# mcu_battery.net
KiCad netlist of a schematic drawn in EAGLE
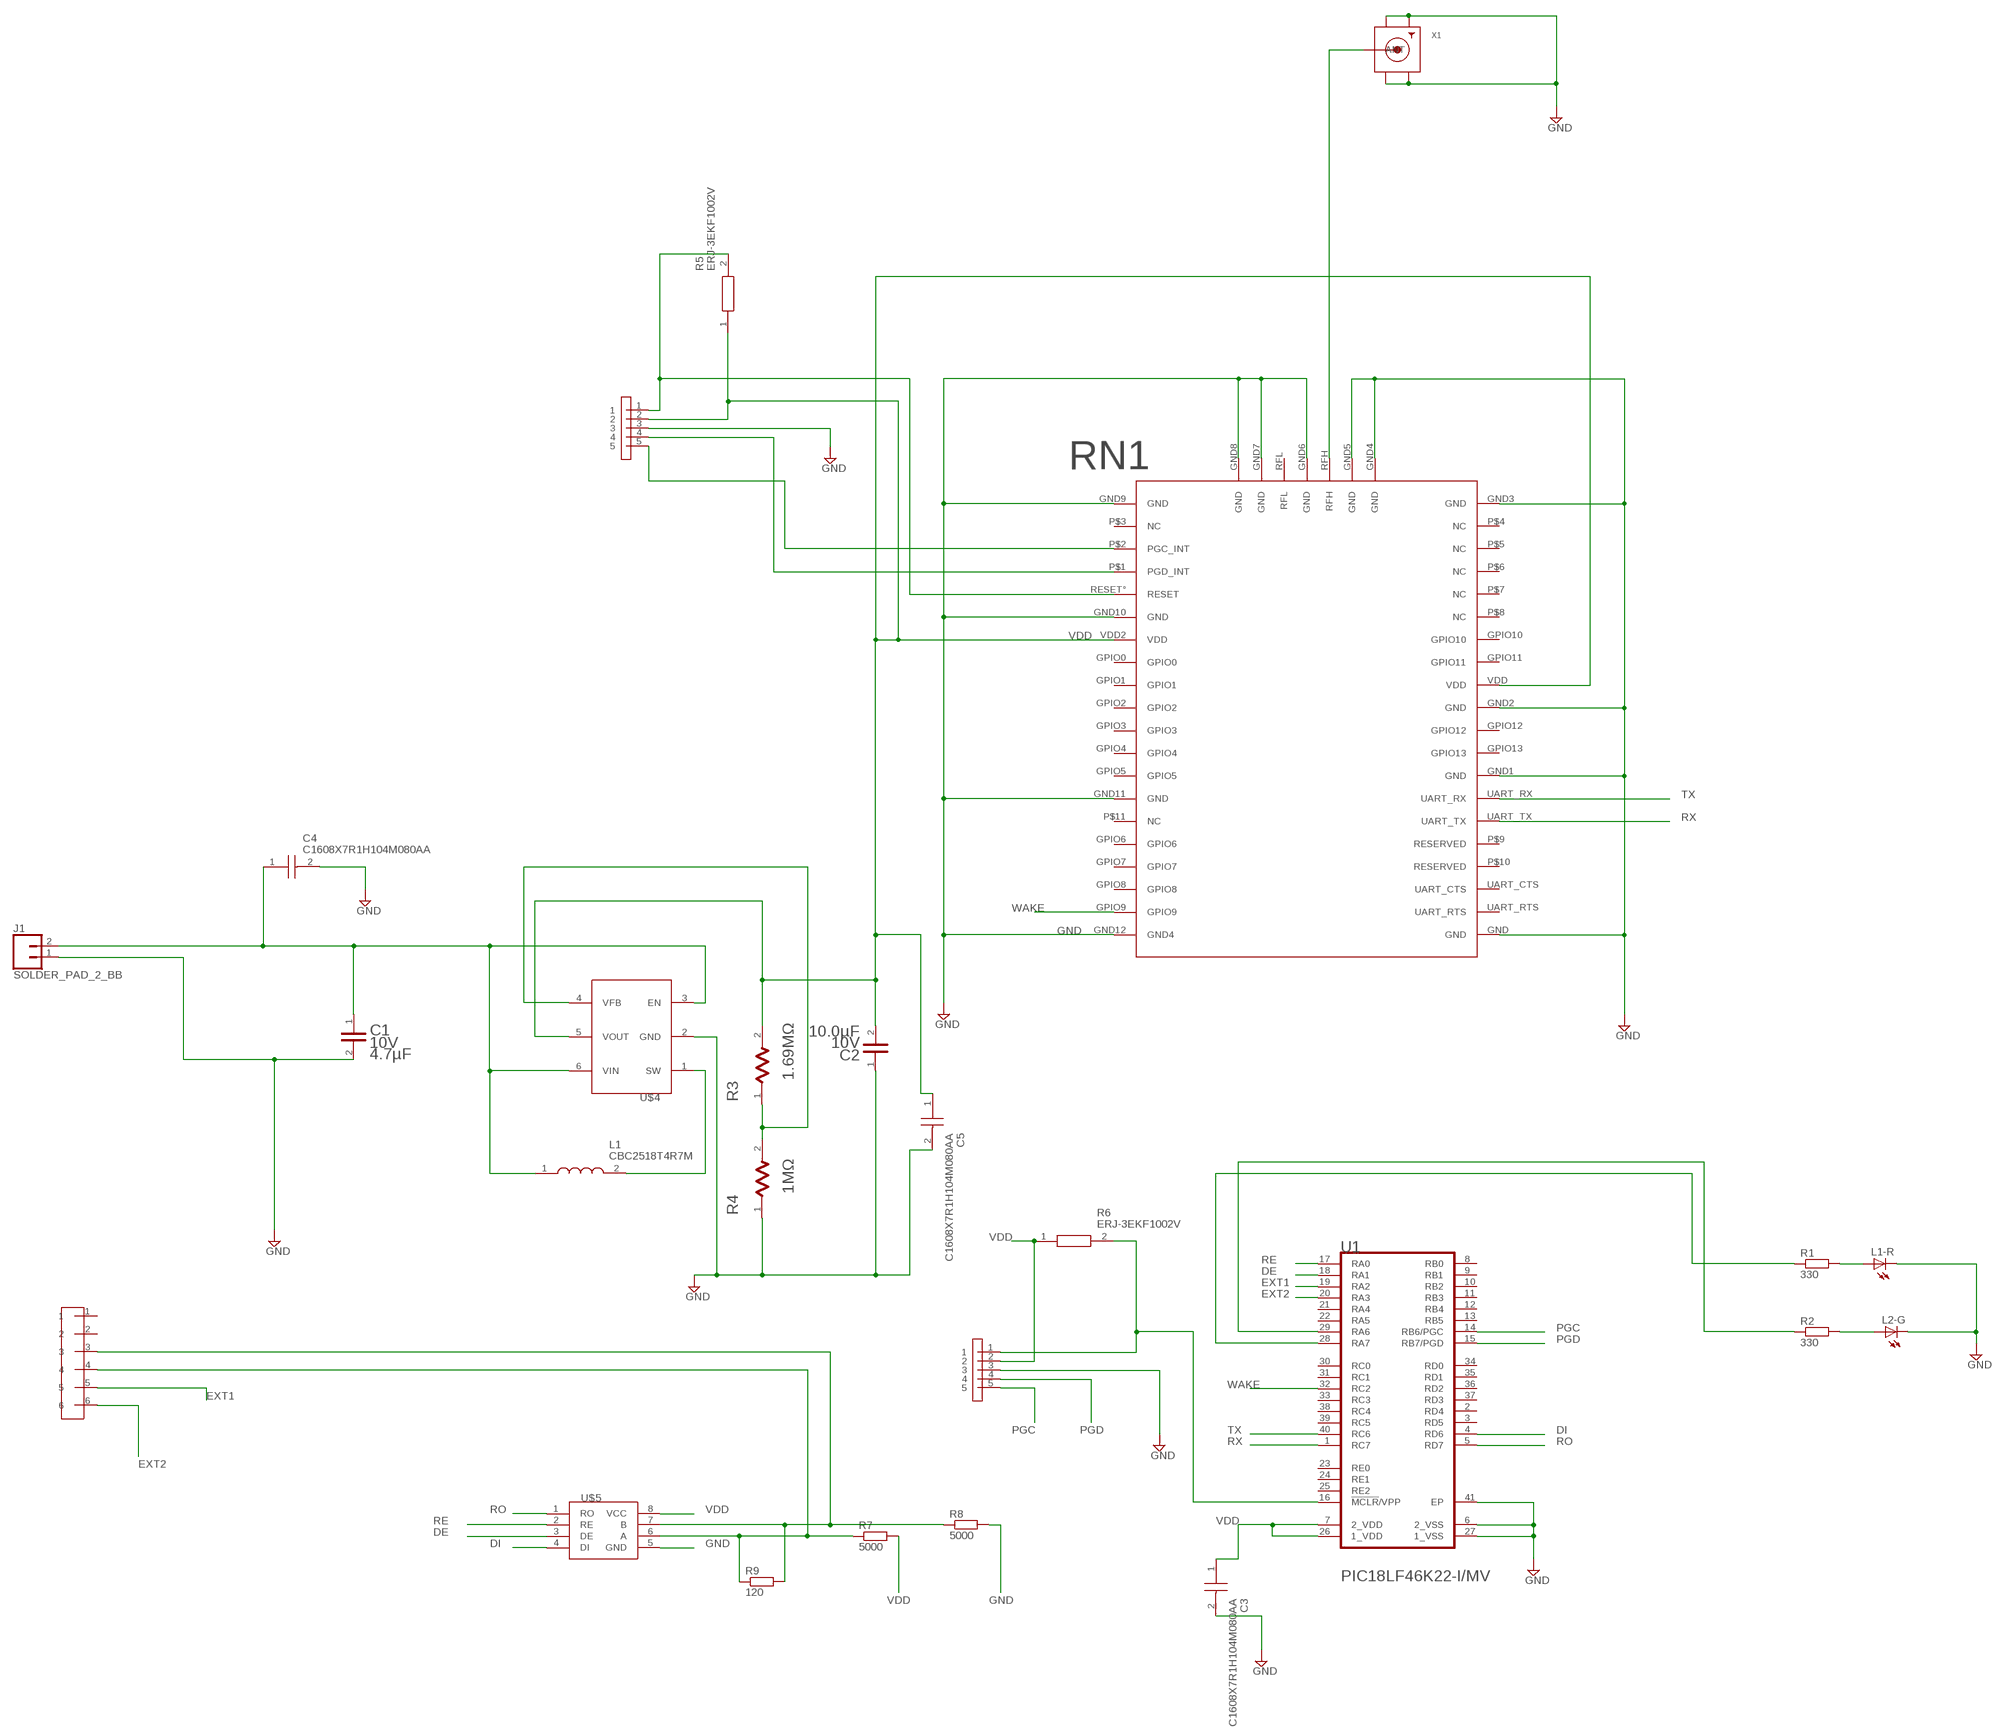
[diagram p0: schematic, sheet 1]

(export (version "E")
  (design (tool "Eeschema 10.0.6"))
  (components
    (comp (ref "C1")
      (value "KEMET_C0603C475K8PACTUKEMET_C0603C475K8PACTU_0_0")
      (footprint "eagle-import:KEMET_C0603C475K8PACTU_0")
      (fields
        (field (name "DIGIKEY_PART_NUMBER") "399-5503-1-ND")
        (field (name "MF") "Kemet")
        (field (name "MOUSER_PART_NUMBER") "80-C0603C475K8P")
      )
      (libsource (lib "eagle-import") (part "KEMET_C0603C475K8PACTUKEMET_C0603C475K8PACTU_0_0"))
    )
    (comp (ref "C2")
      (value "TDK_C1608X5R1A106M080ACTDK_C1608X5R1A106M080AC_0_0")
      (footprint "eagle-import:TDK_C1608X5R1A106M080AC_0")
      (fields
        (field (name "DIGIKEY_PART_NUMBER") "445-6853-1-ND")
        (field (name "MF") "TDK")
        (field (name "MOUSER_PART_NUMBER") "810-C1608X5R1A106M")
      )
      (libsource (lib "eagle-import") (part "TDK_C1608X5R1A106M080ACTDK_C1608X5R1A106M080AC_0_0"))
    )
    (comp (ref "C3")
      (value "C1608X7R1H104M080AA")
      (footprint "eagle-import:CAPC1608X80N")
      (fields (field (name "MOUSER_PART_NUMBER") "810-C1608X7R1H104M"))
      (libsource (lib "eagle-import") (part "C1608X7R1H104M080AA"))
    )
    (comp (ref "C4")
      (value "C1608X7R1H104M080AA")
      (footprint "eagle-import:CAPC1608X80N")
      (fields (field (name "MOUSER_PART_NUMBER") "810-C1608X7R1H104M"))
      (libsource (lib "eagle-import") (part "C1608X7R1H104M080AA"))
    )
    (comp (ref "C5")
      (value "C1608X7R1H104M080AA")
      (footprint "eagle-import:CAPC1608X80N")
      (fields (field (name "MOUSER_PART_NUMBER") "810-C1608X7R1H104M"))
      (libsource (lib "eagle-import") (part "C1608X7R1H104M080AA"))
    )
    (comp (ref "J1")
      (value "SOLDER_PAD_2_BB")
      (footprint "eagle-import:SOLDER_PAD_2")
      (libsource (lib "eagle-import") (part "SOLDER_PAD_2_BB"))
    )
    (comp (ref "L1")
      (value "CBC2518T4R7M")
      (footprint "eagle-import:INDC2518X200N")
      (fields (field (name "MOUSER_PART_NUMBER") "963-CBC2518T4R7M"))
      (libsource (lib "eagle-import") (part "CBC2518T4R7M"))
    )
    (comp (ref "L1-R")
      (value "LEDCHIP-LED0603")
      (footprint "eagle-import:CHIP-LED0603")
      (libsource (lib "eagle-import") (part "LEDCHIP-LED0603"))
    )
    (comp (ref "L2-G")
      (value "LEDCHIP-LED0603")
      (footprint "eagle-import:CHIP-LED0603")
      (libsource (lib "eagle-import") (part "LEDCHIP-LED0603"))
    )
    (comp (ref "R1")
      (value "330")
      (footprint "eagle-import:R0603")
      (libsource (lib "eagle-import") (part "R-EU_R0603"))
    )
    (comp (ref "R2")
      (value "330")
      (footprint "eagle-import:R0603")
      (libsource (lib "eagle-import") (part "R-EU_R0603"))
    )
    (comp (ref "R3")
      (value "VISHAY_CRCW06031M69FKEAVISHAY_CRCW06031M69FKEA_0_1")
      (footprint "eagle-import:VISHAY_CRCW06031M69FKEA_1")
      (fields
        (field (name "APPROVED_ALTERNATE_PART_NUMBER") "541-1.00HHCT-ND")
        (field (name "DIGIKEY_PART_NUMBER") "541-1.69MHTR-ND")
        (field (name "MF") "Vishay")
      )
      (libsource (lib "eagle-import") (part "VISHAY_CRCW06031M69FKEAVISHAY_CRCW06031M69FKEA_0_1"))
    )
    (comp (ref "R4")
      (value "STACKPOLE_RMCF0603FT1M00STACKPOLE_RMCF0603FT1M00_0_1")
      (footprint "eagle-import:STACKPOLE_RMCF0603FT1M00_1")
      (fields
        (field (name "APPROVED_ALTERNATE_PART_NUMBER") "541-1.00HHCT-ND")
        (field (name "DIGIKEY_PART_NUMBER") "RMCF0603FT1M00-ND")
        (field (name "MF") "Stackpole")
      )
      (libsource (lib "eagle-import") (part "STACKPOLE_RMCF0603FT1M00STACKPOLE_RMCF0603FT1M00_0_1"))
    )
    (comp (ref "R5")
      (value "ERJ-3EKF1002V")
      (footprint "eagle-import:RESC1608X55N")
      (fields (field (name "MOUSER_PART_NUMBER") "667-ERJ-3EKF1002V"))
      (libsource (lib "eagle-import") (part "ERJ-3EKF1002V"))
    )
    (comp (ref "R6")
      (value "ERJ-3EKF1002V")
      (footprint "eagle-import:RESC1608X55N")
      (fields (field (name "MOUSER_PART_NUMBER") "667-ERJ-3EKF1002V"))
      (libsource (lib "eagle-import") (part "ERJ-3EKF1002V"))
    )
    (comp (ref "R7")
      (value "5000")
      (footprint "eagle-import:R0805")
      (libsource (lib "eagle-import") (part "R-EU_R0805"))
    )
    (comp (ref "R8")
      (value "5000")
      (footprint "eagle-import:R0805")
      (libsource (lib "eagle-import") (part "R-EU_R0805"))
    )
    (comp (ref "R9")
      (value "120")
      (footprint "eagle-import:R0805")
      (libsource (lib "eagle-import") (part "R-EU_R0805"))
    )
    (comp (ref "RN1")
      (value "NEW_RN2483")
      (footprint "eagle-import:NEW_RN2483")
      (libsource (lib "eagle-import") (part "NEW_RN2483"))
    )
    (comp (ref "U$1")
      (value "CONNECTOR62")
      (footprint "eagle-import:CONNECTOR6")
      (libsource (lib "eagle-import") (part "CONNECTOR62"))
    )
    (comp (ref "U$2")
      (value "ICSP52")
      (footprint "eagle-import:ICSP")
      (libsource (lib "eagle-import") (part "ICSP52"))
    )
    (comp (ref "U$3")
      (value "ICSP52")
      (footprint "eagle-import:ICSP")
      (libsource (lib "eagle-import") (part "ICSP52"))
    )
    (comp (ref "U$4")
      (value "MCP16252")
      (footprint "eagle-import:MCP16252")
      (libsource (lib "eagle-import") (part "MCP16252"))
    )
    (comp (ref "U$5")
      (value "AMD3485E")
      (footprint "eagle-import:AMD3485E")
      (libsource (lib "eagle-import") (part "AMD3485E"))
    )
    (comp (ref "U1")
      (value "MICROCHIP_PIC18LF46K22-I-MVMICROCHIP_PIC18LF46K22-I-MV_0_1")
      (footprint "eagle-import:MICROCHIP_PIC18LF46K22-I-MV_1")
      (fields (field (name "MF") "Microchip") (field (name "MPN") "PIC18LF46K22-I/MV"))
      (libsource (lib "eagle-import") (part "MICROCHIP_PIC18LF46K22-I-MVMICROCHIP_PIC18LF46K22-I-MV_0_1"))
    )
    (comp (ref "X1")
      (value "SMACONNECTOR_EDGE")
      (footprint "eagle-import:SMA_EDGELAUNCH")
      (libsource (lib "eagle-import") (part "SMACONNECTOR_EDGE"))
    )
  )
  (nets
    (net (code "1") (name "/DE") (class "Default")
      (node (ref "U$5") (pin "3") (pinfunction "DE_3") (pintype "bidirectional"))
      (node (ref "U1") (pin "18") (pinfunction "RA1_18") (pintype "bidirectional"))
    )
    (net (code "2") (name "/DI") (class "Default")
      (node (ref "U$5") (pin "4") (pinfunction "DI_4") (pintype "bidirectional"))
      (node (ref "U1") (pin "4") (pinfunction "RD6_4") (pintype "bidirectional"))
    )
    (net (code "3") (name "/EXT1") (class "Default")
      (node (ref "U$1") (pin "5") (pinfunction "5_5") (pintype "bidirectional"))
      (node (ref "U1") (pin "19") (pinfunction "RA2_19") (pintype "bidirectional"))
    )
    (net (code "4") (name "/EXT2") (class "Default")
      (node (ref "U$1") (pin "6") (pinfunction "6_6") (pintype "bidirectional"))
      (node (ref "U1") (pin "20") (pinfunction "RA3_20") (pintype "bidirectional"))
    )
    (net (code "5") (name "/PGC") (class "Default")
      (node (ref "U$2") (pin "5") (pinfunction "5_5") (pintype "bidirectional"))
      (node (ref "U1") (pin "14") (pinfunction "RB6/PGC_14") (pintype "bidirectional"))
    )
    (net (code "6") (name "/PGD") (class "Default")
      (node (ref "U$2") (pin "4") (pinfunction "4_4") (pintype "bidirectional"))
      (node (ref "U1") (pin "15") (pinfunction "RB7/PGD_15") (pintype "bidirectional"))
    )
    (net (code "7") (name "/RE") (class "Default")
      (node (ref "U$5") (pin "2") (pinfunction "RE_2") (pintype "bidirectional"))
      (node (ref "U1") (pin "17") (pinfunction "RA0_17") (pintype "bidirectional"))
    )
    (net (code "8") (name "/RO") (class "Default")
      (node (ref "U$5") (pin "1") (pinfunction "RO_1") (pintype "bidirectional"))
      (node (ref "U1") (pin "5") (pinfunction "RD7_5") (pintype "bidirectional"))
    )
    (net (code "9") (name "/RX") (class "Default")
      (node (ref "RN1") (pin "UART_TX") (pinfunction "UART_TX_UART_TX") (pintype "bidirectional"))
      (node (ref "U1") (pin "1") (pinfunction "RC7_1") (pintype "bidirectional"))
    )
    (net (code "10") (name "/TX") (class "Default")
      (node (ref "RN1") (pin "UART_RX") (pinfunction "UART_RX_UART_RX") (pintype "bidirectional"))
      (node (ref "U1") (pin "40") (pinfunction "RC6_40") (pintype "bidirectional"))
    )
    (net (code "11") (name "/VDD") (class "Default")
      (node (ref "C2") (pin "2") (pinfunction "2_2") (pintype "bidirectional"))
      (node (ref "C3") (pin "1") (pinfunction "1_1") (pintype "bidirectional"))
      (node (ref "C5") (pin "1") (pinfunction "1_1") (pintype "bidirectional"))
      (node (ref "R3") (pin "2") (pinfunction "2_2") (pintype "passive"))
      (node (ref "R5") (pin "1") (pinfunction "1_1") (pintype "bidirectional"))
      (node (ref "R6") (pin "1") (pinfunction "1_1") (pintype "bidirectional"))
      (node (ref "R7") (pin "2") (pinfunction "2_2") (pintype "passive"))
      (node (ref "RN1") (pin "VDD") (pinfunction "VDD_VDD") (pintype "bidirectional"))
      (node (ref "RN1") (pin "VDD2") (pinfunction "VDD_VDD2") (pintype "bidirectional"))
      (node (ref "U$2") (pin "2") (pinfunction "2_2") (pintype "bidirectional"))
      (node (ref "U$3") (pin "2") (pinfunction "2_2") (pintype "bidirectional"))
      (node (ref "U$4") (pin "5") (pinfunction "VOUT_5") (pintype "bidirectional"))
      (node (ref "U$5") (pin "8") (pinfunction "VCC_8") (pintype "bidirectional"))
      (node (ref "U1") (pin "26") (pinfunction "1_VDD_26") (pintype "power_in"))
      (node (ref "U1") (pin "7") (pinfunction "2_VDD_7") (pintype "power_in"))
    )
    (net (code "12") (name "/WAKE") (class "Default")
      (node (ref "RN1") (pin "GPIO9") (pinfunction "GPIO9_GPIO9") (pintype "bidirectional"))
      (node (ref "U1") (pin "32") (pinfunction "RC2_32") (pintype "bidirectional"))
    )
    (net (code "13") (name "GND") (class "Default")
      (node (ref "C1") (pin "2") (pinfunction "2_2") (pintype "bidirectional"))
      (node (ref "C2") (pin "1") (pinfunction "1_1") (pintype "bidirectional"))
      (node (ref "C3") (pin "2") (pinfunction "2_2") (pintype "bidirectional"))
      (node (ref "C4") (pin "2") (pinfunction "2_2") (pintype "bidirectional"))
      (node (ref "C5") (pin "2") (pinfunction "2_2") (pintype "bidirectional"))
      (node (ref "J1") (pin "1") (pinfunction "1_1") (pintype "passive"))
      (node (ref "L1-R") (pin "C") (pinfunction "C_C") (pintype "passive"))
      (node (ref "L2-G") (pin "C") (pinfunction "C_C") (pintype "passive"))
      (node (ref "R4") (pin "1") (pinfunction "1_1") (pintype "passive"))
      (node (ref "R8") (pin "2") (pinfunction "2_2") (pintype "passive"))
      (node (ref "RN1") (pin "GND") (pinfunction "GND_GND") (pintype "bidirectional"))
      (node (ref "RN1") (pin "GND1") (pinfunction "GND_GND1") (pintype "bidirectional"))
      (node (ref "RN1") (pin "GND10") (pinfunction "GND_GND10") (pintype "bidirectional"))
      (node (ref "RN1") (pin "GND11") (pinfunction "GND_GND11") (pintype "bidirectional"))
      (node (ref "RN1") (pin "GND12") (pinfunction "GND4_GND12") (pintype "bidirectional"))
      (node (ref "RN1") (pin "GND2") (pinfunction "GND_GND2") (pintype "bidirectional"))
      (node (ref "RN1") (pin "GND3") (pinfunction "GND_GND3") (pintype "bidirectional"))
      (node (ref "RN1") (pin "GND4") (pinfunction "GND_GND4") (pintype "bidirectional"))
      (node (ref "RN1") (pin "GND5") (pinfunction "GND_GND5") (pintype "bidirectional"))
      (node (ref "RN1") (pin "GND6") (pinfunction "GND_GND6") (pintype "bidirectional"))
      (node (ref "RN1") (pin "GND7") (pinfunction "GND_GND7") (pintype "bidirectional"))
      (node (ref "RN1") (pin "GND8") (pinfunction "GND_GND8") (pintype "bidirectional"))
      (node (ref "RN1") (pin "GND9") (pinfunction "GND_GND9") (pintype "bidirectional"))
      (node (ref "U$2") (pin "3") (pinfunction "3_3") (pintype "bidirectional"))
      (node (ref "U$3") (pin "3") (pinfunction "3_3") (pintype "bidirectional"))
      (node (ref "U$4") (pin "2") (pinfunction "GND_2") (pintype "bidirectional"))
      (node (ref "U$5") (pin "5") (pinfunction "GND_5") (pintype "bidirectional"))
      (node (ref "U1") (pin "27") (pinfunction "1_VSS_27") (pintype "power_in"))
      (node (ref "U1") (pin "41") (pinfunction "EP_41") (pintype "passive"))
      (node (ref "U1") (pin "6") (pinfunction "2_VSS_6") (pintype "power_in"))
      (node (ref "X1") (pin "GND@1") (pinfunction "GND4_GND@1") (pintype "power_in"))
      (node (ref "X1") (pin "GND@2") (pinfunction "GND3_GND@2") (pintype "power_in"))
      (node (ref "X1") (pin "GND@3") (pinfunction "GND2_GND@3") (pintype "power_in"))
      (node (ref "X1") (pin "GND@4") (pinfunction "GND1_GND@4") (pintype "power_in"))
    )
    (net (code "14") (name "Net-(L1-R-PadA)") (class "Default")
      (node (ref "L1-R") (pin "A") (pinfunction "A_A") (pintype "passive"))
      (node (ref "R1") (pin "2") (pinfunction "2_2") (pintype "passive"))
    )
    (net (code "15") (name "Net-(L2-G-PadA)") (class "Default")
      (node (ref "L2-G") (pin "A") (pinfunction "A_A") (pintype "passive"))
      (node (ref "R2") (pin "2") (pinfunction "2_2") (pintype "passive"))
    )
    (net (code "16") (name "Net-(RN1-PGC_INT)") (class "Default")
      (node (ref "RN1") (pin "P$2") (pinfunction "PGC_INT_P$2") (pintype "bidirectional"))
      (node (ref "U$3") (pin "5") (pinfunction "5_5") (pintype "bidirectional"))
    )
    (net (code "17") (name "Net-(RN1-PGD_INT)") (class "Default")
      (node (ref "RN1") (pin "P$1") (pinfunction "PGD_INT_P$1") (pintype "bidirectional"))
      (node (ref "U$3") (pin "4") (pinfunction "4_4") (pintype "bidirectional"))
    )
    (net (code "18") (name "Net-(RN1-RESET)") (class "Default")
      (node (ref "R5") (pin "2") (pinfunction "2_2") (pintype "bidirectional"))
      (node (ref "RN1") (pin "RESET°") (pinfunction "RESET_RESET°") (pintype "bidirectional"))
      (node (ref "U$3") (pin "1") (pinfunction "1_1") (pintype "bidirectional"))
    )
    (net (code "19") (name "Net-(U$4-EN)") (class "Default")
      (node (ref "C1") (pin "1") (pinfunction "1_1") (pintype "bidirectional"))
      (node (ref "C4") (pin "1") (pinfunction "1_1") (pintype "bidirectional"))
      (node (ref "J1") (pin "2") (pinfunction "2_2") (pintype "passive"))
      (node (ref "L1") (pin "1") (pinfunction "1_1") (pintype "bidirectional"))
      (node (ref "U$4") (pin "3") (pinfunction "EN_3") (pintype "bidirectional"))
      (node (ref "U$4") (pin "6") (pinfunction "VIN_6") (pintype "bidirectional"))
    )
    (net (code "20") (name "Net-(U$4-SW)") (class "Default")
      (node (ref "L1") (pin "2") (pinfunction "2_2") (pintype "bidirectional"))
      (node (ref "U$4") (pin "1") (pinfunction "SW_1") (pintype "bidirectional"))
    )
    (net (code "21") (name "Net-(U$4-VFB)") (class "Default")
      (node (ref "R3") (pin "1") (pinfunction "1_1") (pintype "passive"))
      (node (ref "R4") (pin "2") (pinfunction "2_2") (pintype "passive"))
      (node (ref "U$4") (pin "4") (pinfunction "VFB_4") (pintype "bidirectional"))
    )
    (net (code "22") (name "Net-(U$5-A)") (class "Default")
      (node (ref "R7") (pin "1") (pinfunction "1_1") (pintype "passive"))
      (node (ref "R9") (pin "1") (pinfunction "1_1") (pintype "passive"))
      (node (ref "U$1") (pin "4") (pinfunction "4_4") (pintype "bidirectional"))
      (node (ref "U$5") (pin "6") (pinfunction "A_6") (pintype "bidirectional"))
    )
    (net (code "23") (name "Net-(U$5-B)") (class "Default")
      (node (ref "R8") (pin "1") (pinfunction "1_1") (pintype "passive"))
      (node (ref "R9") (pin "2") (pinfunction "2_2") (pintype "passive"))
      (node (ref "U$1") (pin "3") (pinfunction "3_3") (pintype "bidirectional"))
      (node (ref "U$5") (pin "7") (pinfunction "B_7") (pintype "bidirectional"))
    )
    (net (code "24") (name "Net-(U1-RA6)") (class "Default")
      (node (ref "R2") (pin "1") (pinfunction "1_1") (pintype "passive"))
      (node (ref "U1") (pin "29") (pinfunction "RA6_29") (pintype "bidirectional"))
    )
    (net (code "25") (name "Net-(U1-RA7)") (class "Default")
      (node (ref "R1") (pin "1") (pinfunction "1_1") (pintype "passive"))
      (node (ref "U1") (pin "28") (pinfunction "RA7_28") (pintype "bidirectional"))
    )
    (net (code "26") (name "Net-(U1-~{MCLR}{slash}VPP)") (class "Default")
      (node (ref "R6") (pin "2") (pinfunction "2_2") (pintype "bidirectional"))
      (node (ref "U$2") (pin "1") (pinfunction "1_1") (pintype "bidirectional"))
      (node (ref "U1") (pin "16") (pinfunction "~{MCLR}/VPP_16") (pintype "input"))
    )
    (net (code "27") (name "Net-(X1-ANT)") (class "Default")
      (node (ref "RN1") (pin "RFH") (pinfunction "RFH_RFH") (pintype "bidirectional"))
      (node (ref "X1") (pin "P") (pinfunction "ANT_P") (pintype "bidirectional"))
    )
    (net (code "28") (name "unconnected-(RN1-NC-PadP$3)") (class "Default")
      (node (ref "RN1") (pin "P$3") (pinfunction "NC_P$3") (pintype "bidirectional"))
    )
    (net (code "29") (name "unconnected-(RN1-NC-PadP$4)") (class "Default")
      (node (ref "RN1") (pin "P$4") (pinfunction "NC_P$4") (pintype "bidirectional"))
    )
    (net (code "30") (name "unconnected-(RN1-NC-PadP$5)") (class "Default")
      (node (ref "RN1") (pin "P$5") (pinfunction "NC_P$5") (pintype "bidirectional"))
    )
    (net (code "31") (name "unconnected-(RN1-NC-PadP$6)") (class "Default")
      (node (ref "RN1") (pin "P$6") (pinfunction "NC_P$6") (pintype "bidirectional"))
    )
    (net (code "32") (name "unconnected-(RN1-NC-PadP$7)") (class "Default")
      (node (ref "RN1") (pin "P$7") (pinfunction "NC_P$7") (pintype "bidirectional"))
    )
    (net (code "33") (name "unconnected-(RN1-NC-PadP$8)") (class "Default")
      (node (ref "RN1") (pin "P$8") (pinfunction "NC_P$8") (pintype "bidirectional"))
    )
    (net (code "34") (name "unconnected-(RN1-NC-PadP$11)") (class "Default")
      (node (ref "RN1") (pin "P$11") (pinfunction "NC_P$11") (pintype "bidirectional"))
    )
    (net (code "35") (name "unconnected-(RN1-PadGPIO0)") (class "Default")
      (node (ref "RN1") (pin "GPIO0") (pinfunction "GPIO0_GPIO0") (pintype "bidirectional"))
    )
    (net (code "36") (name "unconnected-(RN1-PadGPIO1)") (class "Default")
      (node (ref "RN1") (pin "GPIO1") (pinfunction "GPIO1_GPIO1") (pintype "bidirectional"))
    )
    (net (code "37") (name "unconnected-(RN1-PadGPIO2)") (class "Default")
      (node (ref "RN1") (pin "GPIO2") (pinfunction "GPIO2_GPIO2") (pintype "bidirectional"))
    )
    (net (code "38") (name "unconnected-(RN1-PadGPIO3)") (class "Default")
      (node (ref "RN1") (pin "GPIO3") (pinfunction "GPIO3_GPIO3") (pintype "bidirectional"))
    )
    (net (code "39") (name "unconnected-(RN1-PadGPIO4)") (class "Default")
      (node (ref "RN1") (pin "GPIO4") (pinfunction "GPIO4_GPIO4") (pintype "bidirectional"))
    )
    (net (code "40") (name "unconnected-(RN1-PadGPIO5)") (class "Default")
      (node (ref "RN1") (pin "GPIO5") (pinfunction "GPIO5_GPIO5") (pintype "bidirectional"))
    )
    (net (code "41") (name "unconnected-(RN1-PadGPIO6)") (class "Default")
      (node (ref "RN1") (pin "GPIO6") (pinfunction "GPIO6_GPIO6") (pintype "bidirectional"))
    )
    (net (code "42") (name "unconnected-(RN1-PadGPIO7)") (class "Default")
      (node (ref "RN1") (pin "GPIO7") (pinfunction "GPIO7_GPIO7") (pintype "bidirectional"))
    )
    (net (code "43") (name "unconnected-(RN1-PadGPIO8)") (class "Default")
      (node (ref "RN1") (pin "GPIO8") (pinfunction "GPIO8_GPIO8") (pintype "bidirectional"))
    )
    (net (code "44") (name "unconnected-(RN1-PadGPIO10)") (class "Default")
      (node (ref "RN1") (pin "GPIO10") (pinfunction "GPIO10_GPIO10") (pintype "bidirectional"))
    )
    (net (code "45") (name "unconnected-(RN1-PadGPIO11)") (class "Default")
      (node (ref "RN1") (pin "GPIO11") (pinfunction "GPIO11_GPIO11") (pintype "bidirectional"))
    )
    (net (code "46") (name "unconnected-(RN1-PadGPIO12)") (class "Default")
      (node (ref "RN1") (pin "GPIO12") (pinfunction "GPIO12_GPIO12") (pintype "bidirectional"))
    )
    (net (code "47") (name "unconnected-(RN1-PadGPIO13)") (class "Default")
      (node (ref "RN1") (pin "GPIO13") (pinfunction "GPIO13_GPIO13") (pintype "bidirectional"))
    )
    (net (code "48") (name "unconnected-(RN1-PadRFL)") (class "Default")
      (node (ref "RN1") (pin "RFL") (pinfunction "RFL_RFL") (pintype "bidirectional"))
    )
    (net (code "49") (name "unconnected-(RN1-PadUART_CTS)") (class "Default")
      (node (ref "RN1") (pin "UART_CTS") (pinfunction "UART_CTS_UART_CTS") (pintype "bidirectional"))
    )
    (net (code "50") (name "unconnected-(RN1-PadUART_RTS)") (class "Default")
      (node (ref "RN1") (pin "UART_RTS") (pinfunction "UART_RTS_UART_RTS") (pintype "bidirectional"))
    )
    (net (code "51") (name "unconnected-(RN1-RESERVED-PadP$9)") (class "Default")
      (node (ref "RN1") (pin "P$9") (pinfunction "RESERVED_P$9") (pintype "bidirectional"))
    )
    (net (code "52") (name "unconnected-(RN1-RESERVED-PadP$10)") (class "Default")
      (node (ref "RN1") (pin "P$10") (pinfunction "RESERVED_P$10") (pintype "bidirectional"))
    )
    (net (code "53") (name "unconnected-(U$1-Pad1)") (class "Default")
      (node (ref "U$1") (pin "1") (pinfunction "1_1") (pintype "bidirectional"))
    )
    (net (code "54") (name "unconnected-(U$1-Pad2)") (class "Default")
      (node (ref "U$1") (pin "2") (pinfunction "2_2") (pintype "bidirectional"))
    )
    (net (code "55") (name "unconnected-(U1-RA4-Pad21)") (class "Default")
      (node (ref "U1") (pin "21") (pinfunction "RA4_21") (pintype "bidirectional"))
    )
    (net (code "56") (name "unconnected-(U1-RA5-Pad22)") (class "Default")
      (node (ref "U1") (pin "22") (pinfunction "RA5_22") (pintype "bidirectional"))
    )
    (net (code "57") (name "unconnected-(U1-RB0-Pad8)") (class "Default")
      (node (ref "U1") (pin "8") (pinfunction "RB0_8") (pintype "bidirectional"))
    )
    (net (code "58") (name "unconnected-(U1-RB1-Pad9)") (class "Default")
      (node (ref "U1") (pin "9") (pinfunction "RB1_9") (pintype "bidirectional"))
    )
    (net (code "59") (name "unconnected-(U1-RB2-Pad10)") (class "Default")
      (node (ref "U1") (pin "10") (pinfunction "RB2_10") (pintype "bidirectional"))
    )
    (net (code "60") (name "unconnected-(U1-RB3-Pad11)") (class "Default")
      (node (ref "U1") (pin "11") (pinfunction "RB3_11") (pintype "bidirectional"))
    )
    (net (code "61") (name "unconnected-(U1-RB4-Pad12)") (class "Default")
      (node (ref "U1") (pin "12") (pinfunction "RB4_12") (pintype "bidirectional"))
    )
    (net (code "62") (name "unconnected-(U1-RB5-Pad13)") (class "Default")
      (node (ref "U1") (pin "13") (pinfunction "RB5_13") (pintype "bidirectional"))
    )
    (net (code "63") (name "unconnected-(U1-RC0-Pad30)") (class "Default")
      (node (ref "U1") (pin "30") (pinfunction "RC0_30") (pintype "bidirectional"))
    )
    (net (code "64") (name "unconnected-(U1-RC1-Pad31)") (class "Default")
      (node (ref "U1") (pin "31") (pinfunction "RC1_31") (pintype "bidirectional"))
    )
    (net (code "65") (name "unconnected-(U1-RC3-Pad33)") (class "Default")
      (node (ref "U1") (pin "33") (pinfunction "RC3_33") (pintype "bidirectional"))
    )
    (net (code "66") (name "unconnected-(U1-RC4-Pad38)") (class "Default")
      (node (ref "U1") (pin "38") (pinfunction "RC4_38") (pintype "bidirectional"))
    )
    (net (code "67") (name "unconnected-(U1-RC5-Pad39)") (class "Default")
      (node (ref "U1") (pin "39") (pinfunction "RC5_39") (pintype "bidirectional"))
    )
    (net (code "68") (name "unconnected-(U1-RD0-Pad34)") (class "Default")
      (node (ref "U1") (pin "34") (pinfunction "RD0_34") (pintype "bidirectional"))
    )
    (net (code "69") (name "unconnected-(U1-RD1-Pad35)") (class "Default")
      (node (ref "U1") (pin "35") (pinfunction "RD1_35") (pintype "bidirectional"))
    )
    (net (code "70") (name "unconnected-(U1-RD2-Pad36)") (class "Default")
      (node (ref "U1") (pin "36") (pinfunction "RD2_36") (pintype "bidirectional"))
    )
    (net (code "71") (name "unconnected-(U1-RD3-Pad37)") (class "Default")
      (node (ref "U1") (pin "37") (pinfunction "RD3_37") (pintype "bidirectional"))
    )
    (net (code "72") (name "unconnected-(U1-RD4-Pad2)") (class "Default")
      (node (ref "U1") (pin "2") (pinfunction "RD4_2") (pintype "bidirectional"))
    )
    (net (code "73") (name "unconnected-(U1-RD5-Pad3)") (class "Default")
      (node (ref "U1") (pin "3") (pinfunction "RD5_3") (pintype "bidirectional"))
    )
    (net (code "74") (name "unconnected-(U1-RE0-Pad23)") (class "Default")
      (node (ref "U1") (pin "23") (pinfunction "RE0_23") (pintype "bidirectional"))
    )
    (net (code "75") (name "unconnected-(U1-RE1-Pad24)") (class "Default")
      (node (ref "U1") (pin "24") (pinfunction "RE1_24") (pintype "bidirectional"))
    )
    (net (code "76") (name "unconnected-(U1-RE2-Pad25)") (class "Default")
      (node (ref "U1") (pin "25") (pinfunction "RE2_25") (pintype "bidirectional"))
    )
  )
)
